# BareBonePCB4LED.net
KiCad netlist of a schematic drawn in EAGLE
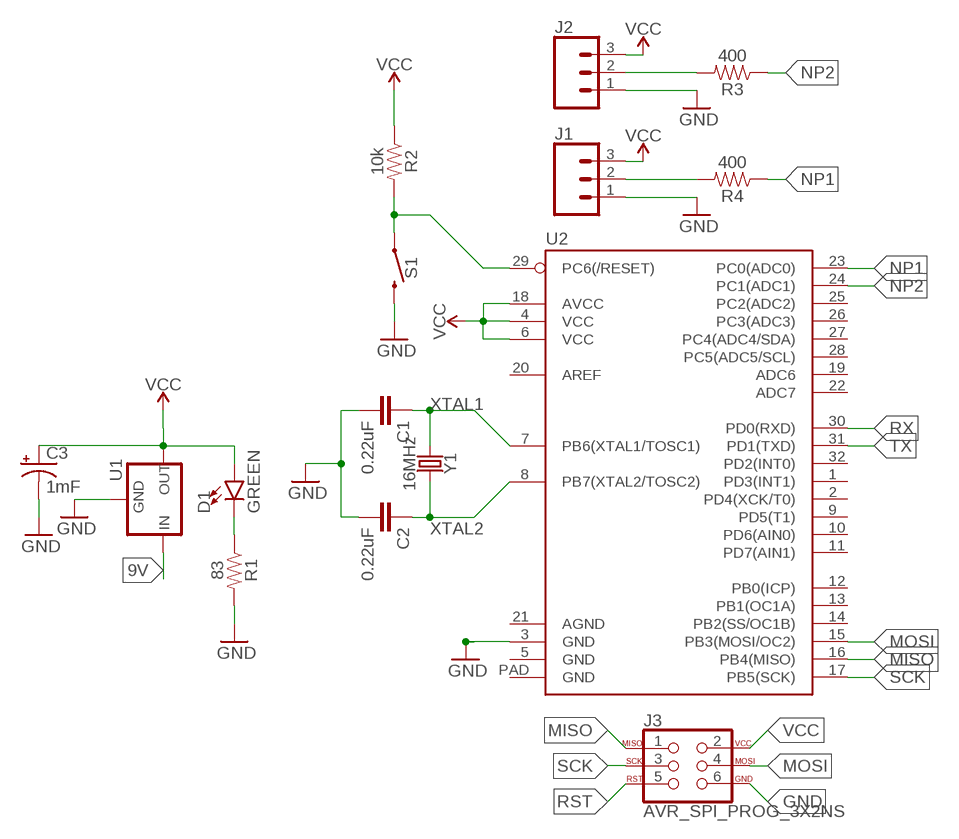
[diagram p0: schematic, sheet 1]

(export (version "E")
  (design (tool "Eeschema 10.0.6"))
  (components
    (comp (ref "C1")
      (value "0.22uF")
      (footprint "eagle-import:0603")
      (libsource (lib "eagle-import") (part "0.22UF-0603-25V-10%"))
    )
    (comp (ref "C2")
      (value "0.22uF")
      (footprint "eagle-import:0603")
      (libsource (lib "eagle-import") (part "0.22UF-0603-25V-10%"))
    )
    (comp (ref "C3")
      (value "1mF")
      (footprint "eagle-import:CPOL-RADIAL-5MM-10MM")
      (libsource (lib "eagle-import") (part "1000UF-RADIAL-5MM-25V-20%"))
    )
    (comp (ref "D1")
      (value "GREEN")
      (footprint "eagle-import:LED-0603")
      (libsource (lib "eagle-import") (part "LED-GREEN0603"))
    )
    (comp (ref "J1")
      (value "CONN_03")
      (footprint "eagle-import:1X03")
      (libsource (lib "eagle-import") (part "CONN_03"))
    )
    (comp (ref "J2")
      (value "CONN_03")
      (footprint "eagle-import:1X03")
      (libsource (lib "eagle-import") (part "CONN_03"))
    )
    (comp (ref "J3")
      (value "AVR_SPI_PROG_3X2NS")
      (footprint "eagle-import:2X3-NS")
      (libsource (lib "eagle-import") (part "AVR_SPI_PROG_3X2NS"))
    )
    (comp (ref "R1")
      (value "83")
      (footprint "eagle-import:0603")
      (libsource (lib "eagle-import") (part "470OHM-0603-1/10W-1%"))
    )
    (comp (ref "R2")
      (value "10k")
      (footprint "eagle-import:0603")
      (libsource (lib "eagle-import") (part "470OHM-0603-1/10W-1%"))
    )
    (comp (ref "R3")
      (value "400")
      (footprint "eagle-import:0603")
      (libsource (lib "eagle-import") (part "470OHM-0603-1/10W-1%"))
    )
    (comp (ref "R4")
      (value "400")
      (footprint "eagle-import:0603")
      (libsource (lib "eagle-import") (part "470OHM-0603-1/10W-1%"))
    )
    (comp (ref "S1")
      (value "MOMENTARY-SWITCH-SPST-PTH-6.0MM-KIT")
      (footprint "eagle-import:TACTILE_SWITCH_PTH_6.0MM_KIT")
      (libsource (lib "eagle-import") (part "MOMENTARY-SWITCH-SPST-PTH-6.0MM-KIT"))
    )
    (comp (ref "U1")
      (value "R-78E5.0-1.0")
      (footprint "eagle-import:DC-DC_CONVERTER_78XX")
      (libsource (lib "eagle-import") (part "R-78E5.0-1.0"))
    )
    (comp (ref "U2")
      (value "ATMEGA328P_MLFMLF32")
      (footprint "eagle-import:MLF32-PAD")
      (libsource (lib "eagle-import") (part "ATMEGA328P_MLFMLF32"))
    )
    (comp (ref "Y1")
      (value "16MHz")
      (footprint "eagle-import:HC49US")
      (libsource (lib "eagle-import") (part "CRYSTAL-16MHZPTH-HC49US"))
    )
  )
  (nets
    (net (code "1") (name "/XTAL1") (class "Default")
      (node (ref "C1") (pin "1") (pinfunction "1_1") (pintype "passive"))
      (node (ref "U2") (pin "7") (pinfunction "PB6(XTAL1/TOSC1)_7") (pintype "bidirectional"))
      (node (ref "Y1") (pin "1") (pinfunction "1_1") (pintype "passive"))
    )
    (net (code "2") (name "/XTAL2") (class "Default")
      (node (ref "C2") (pin "1") (pinfunction "1_1") (pintype "passive"))
      (node (ref "U2") (pin "8") (pinfunction "PB7(XTAL2/TOSC2)_8") (pintype "bidirectional"))
      (node (ref "Y1") (pin "2") (pinfunction "2_2") (pintype "passive"))
    )
    (net (code "3") (name "9V") (class "Default")
      (node (ref "U1") (pin "VIN") (pinfunction "IN_VIN") (pintype "input"))
    )
    (net (code "4") (name "GND") (class "Default")
      (node (ref "C1") (pin "2") (pinfunction "2_2") (pintype "passive"))
      (node (ref "C2") (pin "2") (pinfunction "2_2") (pintype "passive"))
      (node (ref "C3") (pin "-") (pinfunction "-_-") (pintype "passive"))
      (node (ref "J1") (pin "1") (pinfunction "1_1") (pintype "passive"))
      (node (ref "J2") (pin "1") (pinfunction "1_1") (pintype "passive"))
      (node (ref "J3") (pin "6") (pinfunction "6_6") (pintype "passive"))
      (node (ref "R1") (pin "2") (pinfunction "2_2") (pintype "passive"))
      (node (ref "S1") (pin "3") (pinfunction "2_3") (pintype "passive"))
      (node (ref "U1") (pin "GND") (pinfunction "GND_GND") (pintype "input"))
      (node (ref "U2") (pin "3") (pinfunction "GND_3") (pintype "bidirectional"))
    )
    (net (code "5") (name "MISO") (class "Default")
      (node (ref "J3") (pin "1") (pinfunction "1_1") (pintype "passive"))
      (node (ref "U2") (pin "16") (pinfunction "PB4(MISO)_16") (pintype "bidirectional"))
    )
    (net (code "6") (name "MOSI") (class "Default")
      (node (ref "J3") (pin "4") (pinfunction "4_4") (pintype "passive"))
      (node (ref "U2") (pin "15") (pinfunction "PB3(MOSI/OC2)_15") (pintype "bidirectional"))
    )
    (net (code "7") (name "NP1") (class "Default")
      (node (ref "R4") (pin "1") (pinfunction "1_1") (pintype "passive"))
      (node (ref "U2") (pin "23") (pinfunction "PC0(ADC0)_23") (pintype "bidirectional"))
    )
    (net (code "8") (name "NP2") (class "Default")
      (node (ref "R3") (pin "1") (pinfunction "1_1") (pintype "passive"))
      (node (ref "U2") (pin "24") (pinfunction "PC1(ADC1)_24") (pintype "bidirectional"))
    )
    (net (code "9") (name "Net-(D1-PadC)") (class "Default")
      (node (ref "D1") (pin "C") (pinfunction "C_C") (pintype "passive"))
      (node (ref "R1") (pin "1") (pinfunction "1_1") (pintype "passive"))
    )
    (net (code "10") (name "Net-(J1-Pad2)") (class "Default")
      (node (ref "J1") (pin "2") (pinfunction "2_2") (pintype "passive"))
      (node (ref "R4") (pin "2") (pinfunction "2_2") (pintype "passive"))
    )
    (net (code "11") (name "Net-(J2-Pad2)") (class "Default")
      (node (ref "J2") (pin "2") (pinfunction "2_2") (pintype "passive"))
      (node (ref "R3") (pin "2") (pinfunction "2_2") (pintype "passive"))
    )
    (net (code "12") (name "RST") (class "Default")
      (node (ref "J3") (pin "5") (pinfunction "5_5") (pintype "passive"))
      (node (ref "R2") (pin "2") (pinfunction "2_2") (pintype "passive"))
      (node (ref "S1") (pin "1") (pinfunction "1_1") (pintype "passive"))
      (node (ref "U2") (pin "29") (pinfunction "PC6(/RESET)_29") (pintype "bidirectional"))
    )
    (net (code "13") (name "RX") (class "Default")
      (node (ref "U2") (pin "30") (pinfunction "PD0(RXD)_30") (pintype "bidirectional"))
    )
    (net (code "14") (name "SCK") (class "Default")
      (node (ref "J3") (pin "3") (pinfunction "3_3") (pintype "passive"))
      (node (ref "U2") (pin "17") (pinfunction "PB5(SCK)_17") (pintype "bidirectional"))
    )
    (net (code "15") (name "TX") (class "Default")
      (node (ref "U2") (pin "31") (pinfunction "PD1(TXD)_31") (pintype "bidirectional"))
    )
    (net (code "16") (name "VCC") (class "Default")
      (node (ref "C3") (pin "+") (pinfunction "+_+") (pintype "passive"))
      (node (ref "D1") (pin "A") (pinfunction "A_A") (pintype "passive"))
      (node (ref "J1") (pin "3") (pinfunction "3_3") (pintype "passive"))
      (node (ref "J2") (pin "3") (pinfunction "3_3") (pintype "passive"))
      (node (ref "J3") (pin "2") (pinfunction "2_2") (pintype "passive"))
      (node (ref "R2") (pin "1") (pinfunction "1_1") (pintype "passive"))
      (node (ref "U1") (pin "VOUT") (pinfunction "OUT_VOUT") (pintype "passive"))
      (node (ref "U2") (pin "18") (pinfunction "AVCC_18") (pintype "bidirectional"))
      (node (ref "U2") (pin "4") (pinfunction "VCC_4") (pintype "bidirectional"))
      (node (ref "U2") (pin "6") (pinfunction "VCC_6") (pintype "bidirectional"))
    )
    (net (code "17") (name "unconnected-(U2-ADC6-Pad19)") (class "Default")
      (node (ref "U2") (pin "19") (pinfunction "ADC6_19") (pintype "bidirectional"))
    )
    (net (code "18") (name "unconnected-(U2-ADC7-Pad22)") (class "Default")
      (node (ref "U2") (pin "22") (pinfunction "ADC7_22") (pintype "bidirectional"))
    )
    (net (code "19") (name "unconnected-(U2-AGND-Pad21)") (class "Default")
      (node (ref "U2") (pin "21") (pinfunction "AGND_21") (pintype "bidirectional"))
    )
    (net (code "20") (name "unconnected-(U2-AREF-Pad20)") (class "Default")
      (node (ref "U2") (pin "20") (pinfunction "AREF_20") (pintype "bidirectional"))
    )
    (net (code "21") (name "unconnected-(U2-GND-Pad5)") (class "Default")
      (node (ref "U2") (pin "5") (pinfunction "GND_5") (pintype "bidirectional"))
    )
    (net (code "22") (name "unconnected-(U2-GND-PadPAD)") (class "Default")
      (node (ref "U2") (pin "PAD") (pinfunction "GND_PAD") (pintype "bidirectional"))
    )
    (net (code "23") (name "unconnected-(U2-PB0(ICP)-Pad12)") (class "Default")
      (node (ref "U2") (pin "12") (pinfunction "PB0(ICP)_12") (pintype "bidirectional"))
    )
    (net (code "24") (name "unconnected-(U2-PB1(OC1A)-Pad13)") (class "Default")
      (node (ref "U2") (pin "13") (pinfunction "PB1(OC1A)_13") (pintype "bidirectional"))
    )
    (net (code "25") (name "unconnected-(U2-PB2(SS{slash}OC1B)-Pad14)") (class "Default")
      (node (ref "U2") (pin "14") (pinfunction "PB2(SS/OC1B)_14") (pintype "bidirectional"))
    )
    (net (code "26") (name "unconnected-(U2-PC2(ADC2)-Pad25)") (class "Default")
      (node (ref "U2") (pin "25") (pinfunction "PC2(ADC2)_25") (pintype "bidirectional"))
    )
    (net (code "27") (name "unconnected-(U2-PC3(ADC3)-Pad26)") (class "Default")
      (node (ref "U2") (pin "26") (pinfunction "PC3(ADC3)_26") (pintype "bidirectional"))
    )
    (net (code "28") (name "unconnected-(U2-PC4(ADC4{slash}SDA)-Pad27)") (class "Default")
      (node (ref "U2") (pin "27") (pinfunction "PC4(ADC4/SDA)_27") (pintype "bidirectional"))
    )
    (net (code "29") (name "unconnected-(U2-PC5(ADC5{slash}SCL)-Pad28)") (class "Default")
      (node (ref "U2") (pin "28") (pinfunction "PC5(ADC5/SCL)_28") (pintype "bidirectional"))
    )
    (net (code "30") (name "unconnected-(U2-PD2(INT0)-Pad32)") (class "Default")
      (node (ref "U2") (pin "32") (pinfunction "PD2(INT0)_32") (pintype "bidirectional"))
    )
    (net (code "31") (name "unconnected-(U2-PD3(INT1)-Pad1)") (class "Default")
      (node (ref "U2") (pin "1") (pinfunction "PD3(INT1)_1") (pintype "bidirectional"))
    )
    (net (code "32") (name "unconnected-(U2-PD4(XCK{slash}T0)-Pad2)") (class "Default")
      (node (ref "U2") (pin "2") (pinfunction "PD4(XCK/T0)_2") (pintype "bidirectional"))
    )
    (net (code "33") (name "unconnected-(U2-PD5(T1)-Pad9)") (class "Default")
      (node (ref "U2") (pin "9") (pinfunction "PD5(T1)_9") (pintype "bidirectional"))
    )
    (net (code "34") (name "unconnected-(U2-PD6(AIN0)-Pad10)") (class "Default")
      (node (ref "U2") (pin "10") (pinfunction "PD6(AIN0)_10") (pintype "bidirectional"))
    )
    (net (code "35") (name "unconnected-(U2-PD7(AIN1)-Pad11)") (class "Default")
      (node (ref "U2") (pin "11") (pinfunction "PD7(AIN1)_11") (pintype "bidirectional"))
    )
  )
)
